# Thermistor_Interface.net
KiCad netlist of a schematic drawn in Altium Designer
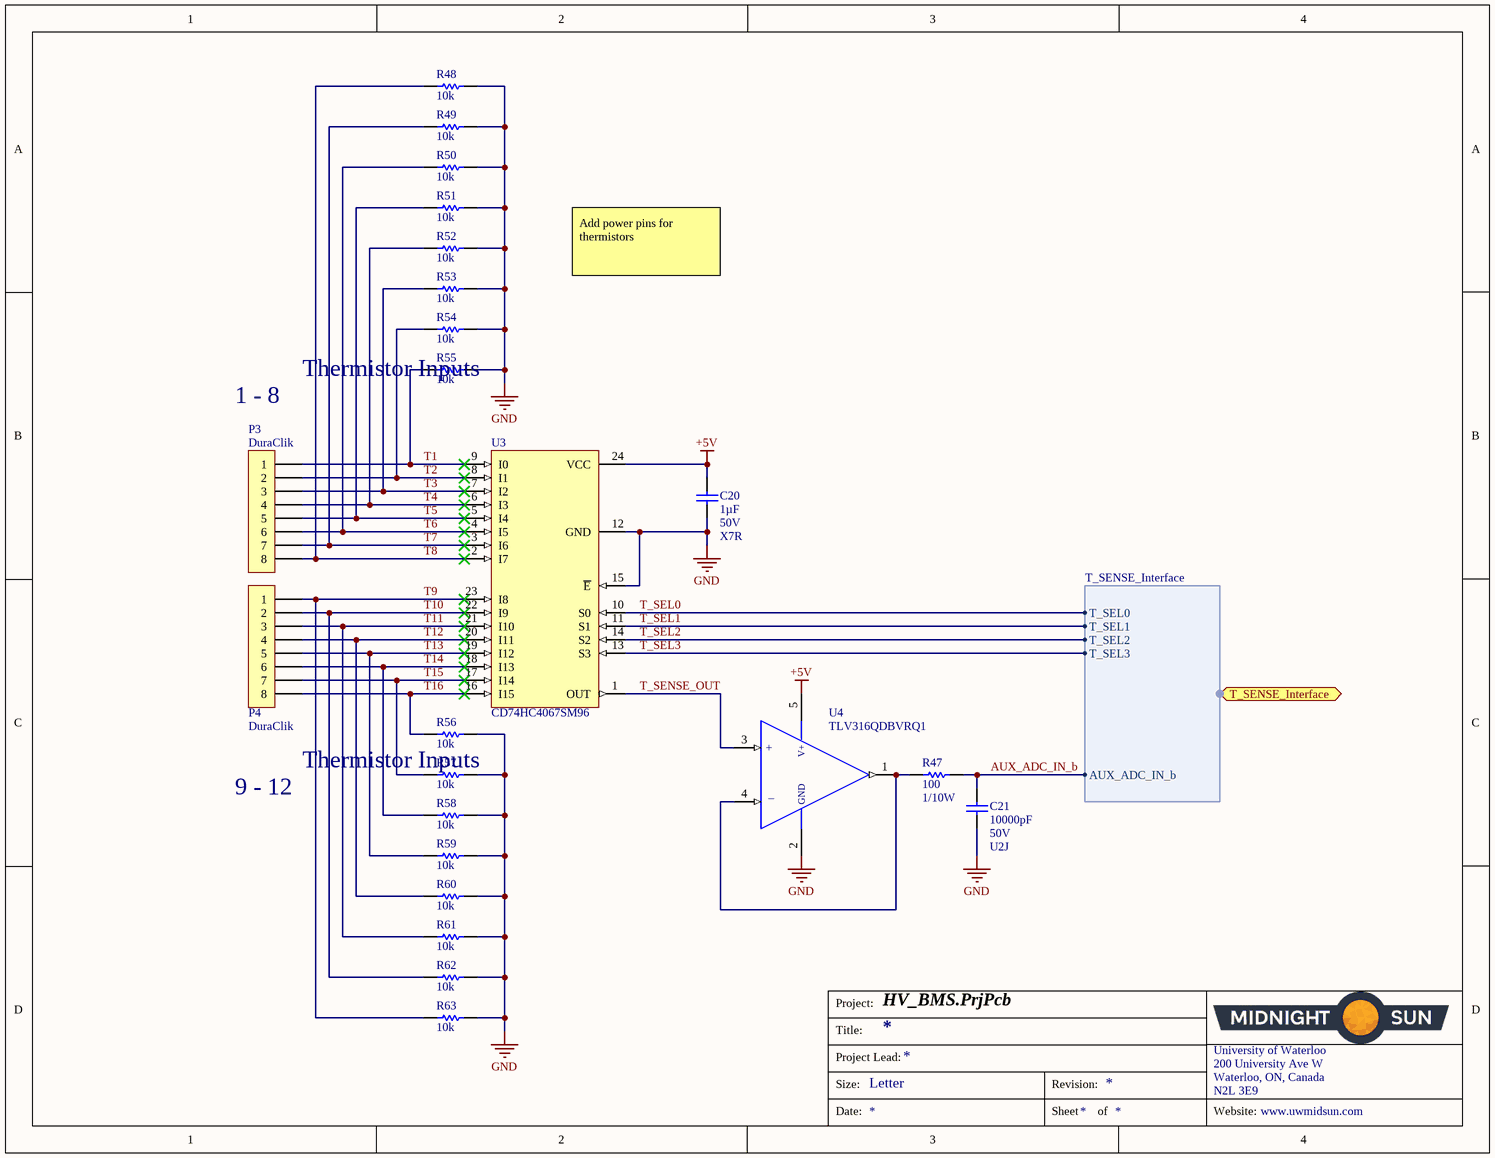
[diagram p0: Thermistor_Interface.SchDoc]

(export (version "E")
  (design (tool "Eeschema 10.0.6"))
  (components
    (comp (ref "C20")
      (value "CAP CER 1UF 50V 10% X7R 0603")
      (footprint "CAP, 0603")
      (description "1µF ±10% 50V Ceramic Capacitor X7R 0603 (1608 Metric)")
      (fields
        (field (name "TOLERANCE") "±10%")
        (field (name "CAPACITANCE") "1µF")
        (field (name "VOLTAGE") "50V")
        (field (name "TEMPERATURE COEFFICIENT") "X7R")
      )
      (libsource (lib "Schematic Diagrams") (part "CAP CER 1UF 50V 10% X7R 0603"))
    )
    (comp (ref "C21")
      (value "CAP CER 10nF 50V 5% X7R 0603")
      (footprint "CAP, 0603")
      (description "10000pF ±5% 50V Ceramic Capacitor U2J 0603 (1608 Metric)")
      (fields
        (field (name "TOLERANCE") "±5%")
        (field (name "CAPACITANCE") "10000pF")
        (field (name "VOLTAGE") "50V")
        (field (name "TEMPERATURE COEFFICIENT") "U2J")
      )
      (libsource (lib "Schematic Diagrams") (part "CAP CER 10nF 50V 5% X7R 0603"))
    )
    (comp (ref "P3")
      (value "CONN 8POS DURA-CLIK 0.079\"")
      (description "8 Positions Header Connector 0.079\" (2.00mm) Surface Mount Tin")
      (fields (field (name "SERIES") "DuraClik"))
      (libsource (lib "Schematic Diagrams") (part "CONN 8POS DURA-CLIK 0.079{dblquote}"))
    )
    (comp (ref "P4")
      (value "CONN 8POS DURA-CLIK 0.079\"")
      (description "8 Positions Header Connector 0.079\" (2.00mm) Surface Mount Tin")
      (fields (field (name "SERIES") "DuraClik"))
      (libsource (lib "Schematic Diagrams") (part "CONN 8POS DURA-CLIK 0.079{dblquote}"))
    )
    (comp (ref "R47")
      (value "RES 100 OHM 1% 1/10W 0603")
      (footprint "RES, 0603")
      (description "100 Ohm ±1% 0.1W, 1/10W Chip Resistor 0603 (1608 Metric) Moisture Resistant Thick Film")
      (fields
        (field (name "TOLERANCE") "±1%")
        (field (name "RESISTANCE") "100")
        (field (name "POWER") "1/10W")
      )
      (libsource (lib "Schematic Diagrams") (part "RES 100 OHM 1% 1/10W 0603"))
    )
    (comp (ref "R48")
      (value "RES 10K OHM 1% 1/10W 0603")
      (footprint "RES, 0603")
      (description "RES SMD 10K OHM 1% 1/10W 0603")
      (fields
        (field (name "TOLERANCE") "±1%")
        (field (name "RESISTANCE") "10k")
        (field (name "POWER") "1/10W")
      )
      (libsource (lib "Schematic Diagrams") (part "RES 10K OHM 1% 1/10W 0603"))
    )
    (comp (ref "R49")
      (value "RES 10K OHM 1% 1/10W 0603")
      (footprint "RES, 0603")
      (description "RES SMD 10K OHM 1% 1/10W 0603")
      (fields
        (field (name "TOLERANCE") "±1%")
        (field (name "RESISTANCE") "10k")
        (field (name "POWER") "1/10W")
      )
      (libsource (lib "Schematic Diagrams") (part "RES 10K OHM 1% 1/10W 0603"))
    )
    (comp (ref "R50")
      (value "RES 10K OHM 1% 1/10W 0603")
      (footprint "RES, 0603")
      (description "RES SMD 10K OHM 1% 1/10W 0603")
      (fields
        (field (name "TOLERANCE") "±1%")
        (field (name "RESISTANCE") "10k")
        (field (name "POWER") "1/10W")
      )
      (libsource (lib "Schematic Diagrams") (part "RES 10K OHM 1% 1/10W 0603"))
    )
    (comp (ref "R51")
      (value "RES 10K OHM 1% 1/10W 0603")
      (footprint "RES, 0603")
      (description "RES SMD 10K OHM 1% 1/10W 0603")
      (fields
        (field (name "TOLERANCE") "±1%")
        (field (name "RESISTANCE") "10k")
        (field (name "POWER") "1/10W")
      )
      (libsource (lib "Schematic Diagrams") (part "RES 10K OHM 1% 1/10W 0603"))
    )
    (comp (ref "R52")
      (value "RES 10K OHM 1% 1/10W 0603")
      (footprint "RES, 0603")
      (description "RES SMD 10K OHM 1% 1/10W 0603")
      (fields
        (field (name "TOLERANCE") "±1%")
        (field (name "RESISTANCE") "10k")
        (field (name "POWER") "1/10W")
      )
      (libsource (lib "Schematic Diagrams") (part "RES 10K OHM 1% 1/10W 0603"))
    )
    (comp (ref "R53")
      (value "RES 10K OHM 1% 1/10W 0603")
      (footprint "RES, 0603")
      (description "RES SMD 10K OHM 1% 1/10W 0603")
      (fields
        (field (name "TOLERANCE") "±1%")
        (field (name "RESISTANCE") "10k")
        (field (name "POWER") "1/10W")
      )
      (libsource (lib "Schematic Diagrams") (part "RES 10K OHM 1% 1/10W 0603"))
    )
    (comp (ref "R54")
      (value "RES 10K OHM 1% 1/10W 0603")
      (footprint "RES, 0603")
      (description "RES SMD 10K OHM 1% 1/10W 0603")
      (fields
        (field (name "TOLERANCE") "±1%")
        (field (name "RESISTANCE") "10k")
        (field (name "POWER") "1/10W")
      )
      (libsource (lib "Schematic Diagrams") (part "RES 10K OHM 1% 1/10W 0603"))
    )
    (comp (ref "R55")
      (value "RES 10K OHM 1% 1/10W 0603")
      (footprint "RES, 0603")
      (description "RES SMD 10K OHM 1% 1/10W 0603")
      (fields
        (field (name "TOLERANCE") "±1%")
        (field (name "RESISTANCE") "10k")
        (field (name "POWER") "1/10W")
      )
      (libsource (lib "Schematic Diagrams") (part "RES 10K OHM 1% 1/10W 0603"))
    )
    (comp (ref "R56")
      (value "RES 10K OHM 1% 1/10W 0603")
      (footprint "RES, 0603")
      (description "RES SMD 10K OHM 1% 1/10W 0603")
      (fields
        (field (name "TOLERANCE") "±1%")
        (field (name "RESISTANCE") "10k")
        (field (name "POWER") "1/10W")
      )
      (libsource (lib "Schematic Diagrams") (part "RES 10K OHM 1% 1/10W 0603"))
    )
    (comp (ref "R57")
      (value "RES 10K OHM 1% 1/10W 0603")
      (footprint "RES, 0603")
      (description "RES SMD 10K OHM 1% 1/10W 0603")
      (fields
        (field (name "TOLERANCE") "±1%")
        (field (name "RESISTANCE") "10k")
        (field (name "POWER") "1/10W")
      )
      (libsource (lib "Schematic Diagrams") (part "RES 10K OHM 1% 1/10W 0603"))
    )
    (comp (ref "R58")
      (value "RES 10K OHM 1% 1/10W 0603")
      (footprint "RES, 0603")
      (description "RES SMD 10K OHM 1% 1/10W 0603")
      (fields
        (field (name "TOLERANCE") "±1%")
        (field (name "RESISTANCE") "10k")
        (field (name "POWER") "1/10W")
      )
      (libsource (lib "Schematic Diagrams") (part "RES 10K OHM 1% 1/10W 0603"))
    )
    (comp (ref "R59")
      (value "RES 10K OHM 1% 1/10W 0603")
      (footprint "RES, 0603")
      (description "RES SMD 10K OHM 1% 1/10W 0603")
      (fields
        (field (name "TOLERANCE") "±1%")
        (field (name "RESISTANCE") "10k")
        (field (name "POWER") "1/10W")
      )
      (libsource (lib "Schematic Diagrams") (part "RES 10K OHM 1% 1/10W 0603"))
    )
    (comp (ref "R60")
      (value "RES 10K OHM 1% 1/10W 0603")
      (footprint "RES, 0603")
      (description "RES SMD 10K OHM 1% 1/10W 0603")
      (fields
        (field (name "TOLERANCE") "±1%")
        (field (name "RESISTANCE") "10k")
        (field (name "POWER") "1/10W")
      )
      (libsource (lib "Schematic Diagrams") (part "RES 10K OHM 1% 1/10W 0603"))
    )
    (comp (ref "R61")
      (value "RES 10K OHM 1% 1/10W 0603")
      (footprint "RES, 0603")
      (description "RES SMD 10K OHM 1% 1/10W 0603")
      (fields
        (field (name "TOLERANCE") "±1%")
        (field (name "RESISTANCE") "10k")
        (field (name "POWER") "1/10W")
      )
      (libsource (lib "Schematic Diagrams") (part "RES 10K OHM 1% 1/10W 0603"))
    )
    (comp (ref "R62")
      (value "RES 10K OHM 1% 1/10W 0603")
      (footprint "RES, 0603")
      (description "RES SMD 10K OHM 1% 1/10W 0603")
      (fields
        (field (name "TOLERANCE") "±1%")
        (field (name "RESISTANCE") "10k")
        (field (name "POWER") "1/10W")
      )
      (libsource (lib "Schematic Diagrams") (part "RES 10K OHM 1% 1/10W 0603"))
    )
    (comp (ref "R63")
      (value "RES 10K OHM 1% 1/10W 0603")
      (footprint "RES, 0603")
      (description "RES SMD 10K OHM 1% 1/10W 0603")
      (fields
        (field (name "TOLERANCE") "±1%")
        (field (name "RESISTANCE") "10k")
        (field (name "POWER") "1/10W")
      )
      (libsource (lib "Schematic Diagrams") (part "RES 10K OHM 1% 1/10W 0603"))
    )
    (comp (ref "U3")
      (value "IC MUX/DEMUX 1X16 24SSOP")
      (description "1 Circuit IC Switch 16:1 160 Ohm 24-SSOP")
      (fields (field (name "MANUFACTURER PART NUMBER 1") "CD74HC4067SM96"))
      (libsource (lib "Schematic Diagrams") (part "IC MUX/DEMUX 1X16 24SSOP"))
    )
    (comp (ref "U4")
      (value "~")
      (footprint "IC OP AMP GP RR 10MHZ SOT-23-5")
      (description "General Purpose Amplifier 1 Circuit Rail-to-Rail SOT-23-5")
      (fields (field (name "MANUFACTURER PART NUMBER 1") "TLV316QDBVRQ1"))
      (libsource (lib "Schematic Diagrams") (part "IC OP AMP GEN PURPOSE RR 10MHZ SOT-23-5"))
    )
  )
  (nets
    (net (code "2") (name "+5V") (class "Default")
      (node (ref "C20") (pin "1") (pinfunction "1_1") (pintype "passive"))
      (node (ref "U3") (pin "24") (pinfunction "VCC_24") (pintype "power_in"))
      (node (ref "U4") (pin "5") (pinfunction "VDD_5") (pintype "power_in"))
    )
    (net (code "3") (name "/AUX_ADC_IN_b") (class "Default")
      (node (ref "C21") (pin "1") (pinfunction "1_1") (pintype "passive"))
      (node (ref "R47") (pin "2") (pinfunction "2_2") (pintype "passive"))
    )
    (net (code "4") (name "/T1") (class "Default")
      (node (ref "P3") (pin "1") (pinfunction "1_1") (pintype "passive"))
      (node (ref "R55") (pin "1") (pinfunction "1_1") (pintype "passive"))
      (node (ref "U3") (pin "9") (pinfunction "I0_9") (pintype "input"))
    )
    (net (code "5") (name "/T2") (class "Default")
      (node (ref "P3") (pin "2") (pinfunction "2_2") (pintype "passive"))
      (node (ref "R54") (pin "1") (pinfunction "1_1") (pintype "passive"))
      (node (ref "U3") (pin "8") (pinfunction "I1_8") (pintype "input"))
    )
    (net (code "6") (name "/T3") (class "Default")
      (node (ref "P3") (pin "3") (pinfunction "3_3") (pintype "passive"))
      (node (ref "R53") (pin "1") (pinfunction "1_1") (pintype "passive"))
      (node (ref "U3") (pin "7") (pinfunction "I2_7") (pintype "input"))
    )
    (net (code "7") (name "/T4") (class "Default")
      (node (ref "P3") (pin "4") (pinfunction "4_4") (pintype "passive"))
      (node (ref "R52") (pin "1") (pinfunction "1_1") (pintype "passive"))
      (node (ref "U3") (pin "6") (pinfunction "I3_6") (pintype "input"))
    )
    (net (code "8") (name "/T5") (class "Default")
      (node (ref "P3") (pin "5") (pinfunction "5_5") (pintype "passive"))
      (node (ref "R51") (pin "1") (pinfunction "1_1") (pintype "passive"))
      (node (ref "U3") (pin "5") (pinfunction "I4_5") (pintype "input"))
    )
    (net (code "9") (name "/T6") (class "Default")
      (node (ref "P3") (pin "6") (pinfunction "6_6") (pintype "passive"))
      (node (ref "R50") (pin "1") (pinfunction "1_1") (pintype "passive"))
      (node (ref "U3") (pin "4") (pinfunction "I5_4") (pintype "input"))
    )
    (net (code "10") (name "/T7") (class "Default")
      (node (ref "P3") (pin "7") (pinfunction "7_7") (pintype "passive"))
      (node (ref "R49") (pin "1") (pinfunction "1_1") (pintype "passive"))
      (node (ref "U3") (pin "3") (pinfunction "I6_3") (pintype "input"))
    )
    (net (code "11") (name "/T8") (class "Default")
      (node (ref "P3") (pin "8") (pinfunction "8_8") (pintype "passive"))
      (node (ref "R48") (pin "1") (pinfunction "1_1") (pintype "passive"))
      (node (ref "U3") (pin "2") (pinfunction "I7_2") (pintype "input"))
    )
    (net (code "12") (name "/T9") (class "Default")
      (node (ref "P4") (pin "1") (pinfunction "1_1") (pintype "passive"))
      (node (ref "R63") (pin "1") (pinfunction "1_1") (pintype "passive"))
      (node (ref "U3") (pin "23") (pinfunction "I8_23") (pintype "input"))
    )
    (net (code "13") (name "/T10") (class "Default")
      (node (ref "P4") (pin "2") (pinfunction "2_2") (pintype "passive"))
      (node (ref "R62") (pin "1") (pinfunction "1_1") (pintype "passive"))
      (node (ref "U3") (pin "22") (pinfunction "I9_22") (pintype "input"))
    )
    (net (code "14") (name "/T11") (class "Default")
      (node (ref "P4") (pin "3") (pinfunction "3_3") (pintype "passive"))
      (node (ref "R61") (pin "1") (pinfunction "1_1") (pintype "passive"))
      (node (ref "U3") (pin "21") (pinfunction "I10_21") (pintype "input"))
    )
    (net (code "15") (name "/T12") (class "Default")
      (node (ref "P4") (pin "4") (pinfunction "4_4") (pintype "passive"))
      (node (ref "R60") (pin "1") (pinfunction "1_1") (pintype "passive"))
      (node (ref "U3") (pin "20") (pinfunction "I11_20") (pintype "input"))
    )
    (net (code "16") (name "/T13") (class "Default")
      (node (ref "P4") (pin "5") (pinfunction "5_5") (pintype "passive"))
      (node (ref "R59") (pin "1") (pinfunction "1_1") (pintype "passive"))
      (node (ref "U3") (pin "19") (pinfunction "I12_19") (pintype "input"))
    )
    (net (code "17") (name "/T14") (class "Default")
      (node (ref "P4") (pin "6") (pinfunction "6_6") (pintype "passive"))
      (node (ref "R58") (pin "1") (pinfunction "1_1") (pintype "passive"))
      (node (ref "U3") (pin "18") (pinfunction "I13_18") (pintype "input"))
    )
    (net (code "18") (name "/T15") (class "Default")
      (node (ref "P4") (pin "7") (pinfunction "7_7") (pintype "passive"))
      (node (ref "R57") (pin "1") (pinfunction "1_1") (pintype "passive"))
      (node (ref "U3") (pin "17") (pinfunction "I14_17") (pintype "input"))
    )
    (net (code "19") (name "/T16") (class "Default")
      (node (ref "P4") (pin "8") (pinfunction "8_8") (pintype "passive"))
      (node (ref "R56") (pin "1") (pinfunction "1_1") (pintype "passive"))
      (node (ref "U3") (pin "16") (pinfunction "I15_16") (pintype "input"))
    )
    (net (code "20") (name "/T_SEL0") (class "Default")
      (node (ref "U3") (pin "10") (pinfunction "S0_10") (pintype "input"))
    )
    (net (code "21") (name "/T_SEL1") (class "Default")
      (node (ref "U3") (pin "11") (pinfunction "S1_11") (pintype "input"))
    )
    (net (code "22") (name "/T_SEL2") (class "Default")
      (node (ref "U3") (pin "14") (pinfunction "S2_14") (pintype "input"))
    )
    (net (code "23") (name "/T_SEL3") (class "Default")
      (node (ref "U3") (pin "13") (pinfunction "S3_13") (pintype "input"))
    )
    (net (code "24") (name "/T_SENSE_OUT") (class "Default")
      (node (ref "U3") (pin "1") (pinfunction "OUT_1") (pintype "output"))
      (node (ref "U4") (pin "3") (pinfunction "+IN_3") (pintype "input"))
    )
    (net (code "26") (name "GND") (class "Default")
      (node (ref "C20") (pin "2") (pinfunction "2_2") (pintype "passive"))
      (node (ref "C21") (pin "2") (pinfunction "2_2") (pintype "passive"))
      (node (ref "R48") (pin "2") (pinfunction "2_2") (pintype "passive"))
      (node (ref "R49") (pin "2") (pinfunction "2_2") (pintype "passive"))
      (node (ref "R50") (pin "2") (pinfunction "2_2") (pintype "passive"))
      (node (ref "R51") (pin "2") (pinfunction "2_2") (pintype "passive"))
      (node (ref "R52") (pin "2") (pinfunction "2_2") (pintype "passive"))
      (node (ref "R53") (pin "2") (pinfunction "2_2") (pintype "passive"))
      (node (ref "R54") (pin "2") (pinfunction "2_2") (pintype "passive"))
      (node (ref "R55") (pin "2") (pinfunction "2_2") (pintype "passive"))
      (node (ref "R56") (pin "2") (pinfunction "2_2") (pintype "passive"))
      (node (ref "R57") (pin "2") (pinfunction "2_2") (pintype "passive"))
      (node (ref "R58") (pin "2") (pinfunction "2_2") (pintype "passive"))
      (node (ref "R59") (pin "2") (pinfunction "2_2") (pintype "passive"))
      (node (ref "R60") (pin "2") (pinfunction "2_2") (pintype "passive"))
      (node (ref "R61") (pin "2") (pinfunction "2_2") (pintype "passive"))
      (node (ref "R62") (pin "2") (pinfunction "2_2") (pintype "passive"))
      (node (ref "R63") (pin "2") (pinfunction "2_2") (pintype "passive"))
      (node (ref "U3") (pin "12") (pinfunction "GND_12") (pintype "power_in"))
      (node (ref "U3") (pin "15") (pinfunction "~{E}_15") (pintype "input"))
      (node (ref "U4") (pin "2") (pinfunction "VSS_2") (pintype "power_in"))
    )
    (net (code "27") (name "Net-(U4--IN)") (class "Default")
      (node (ref "R47") (pin "1") (pinfunction "1_1") (pintype "passive"))
      (node (ref "U4") (pin "1") (pinfunction "OUTPUT_1") (pintype "output"))
      (node (ref "U4") (pin "4") (pinfunction "-IN_4") (pintype "input"))
    )
  )
)
